# Brain_0_1_rv1.net
KiCad netlist of a schematic drawn in EAGLE
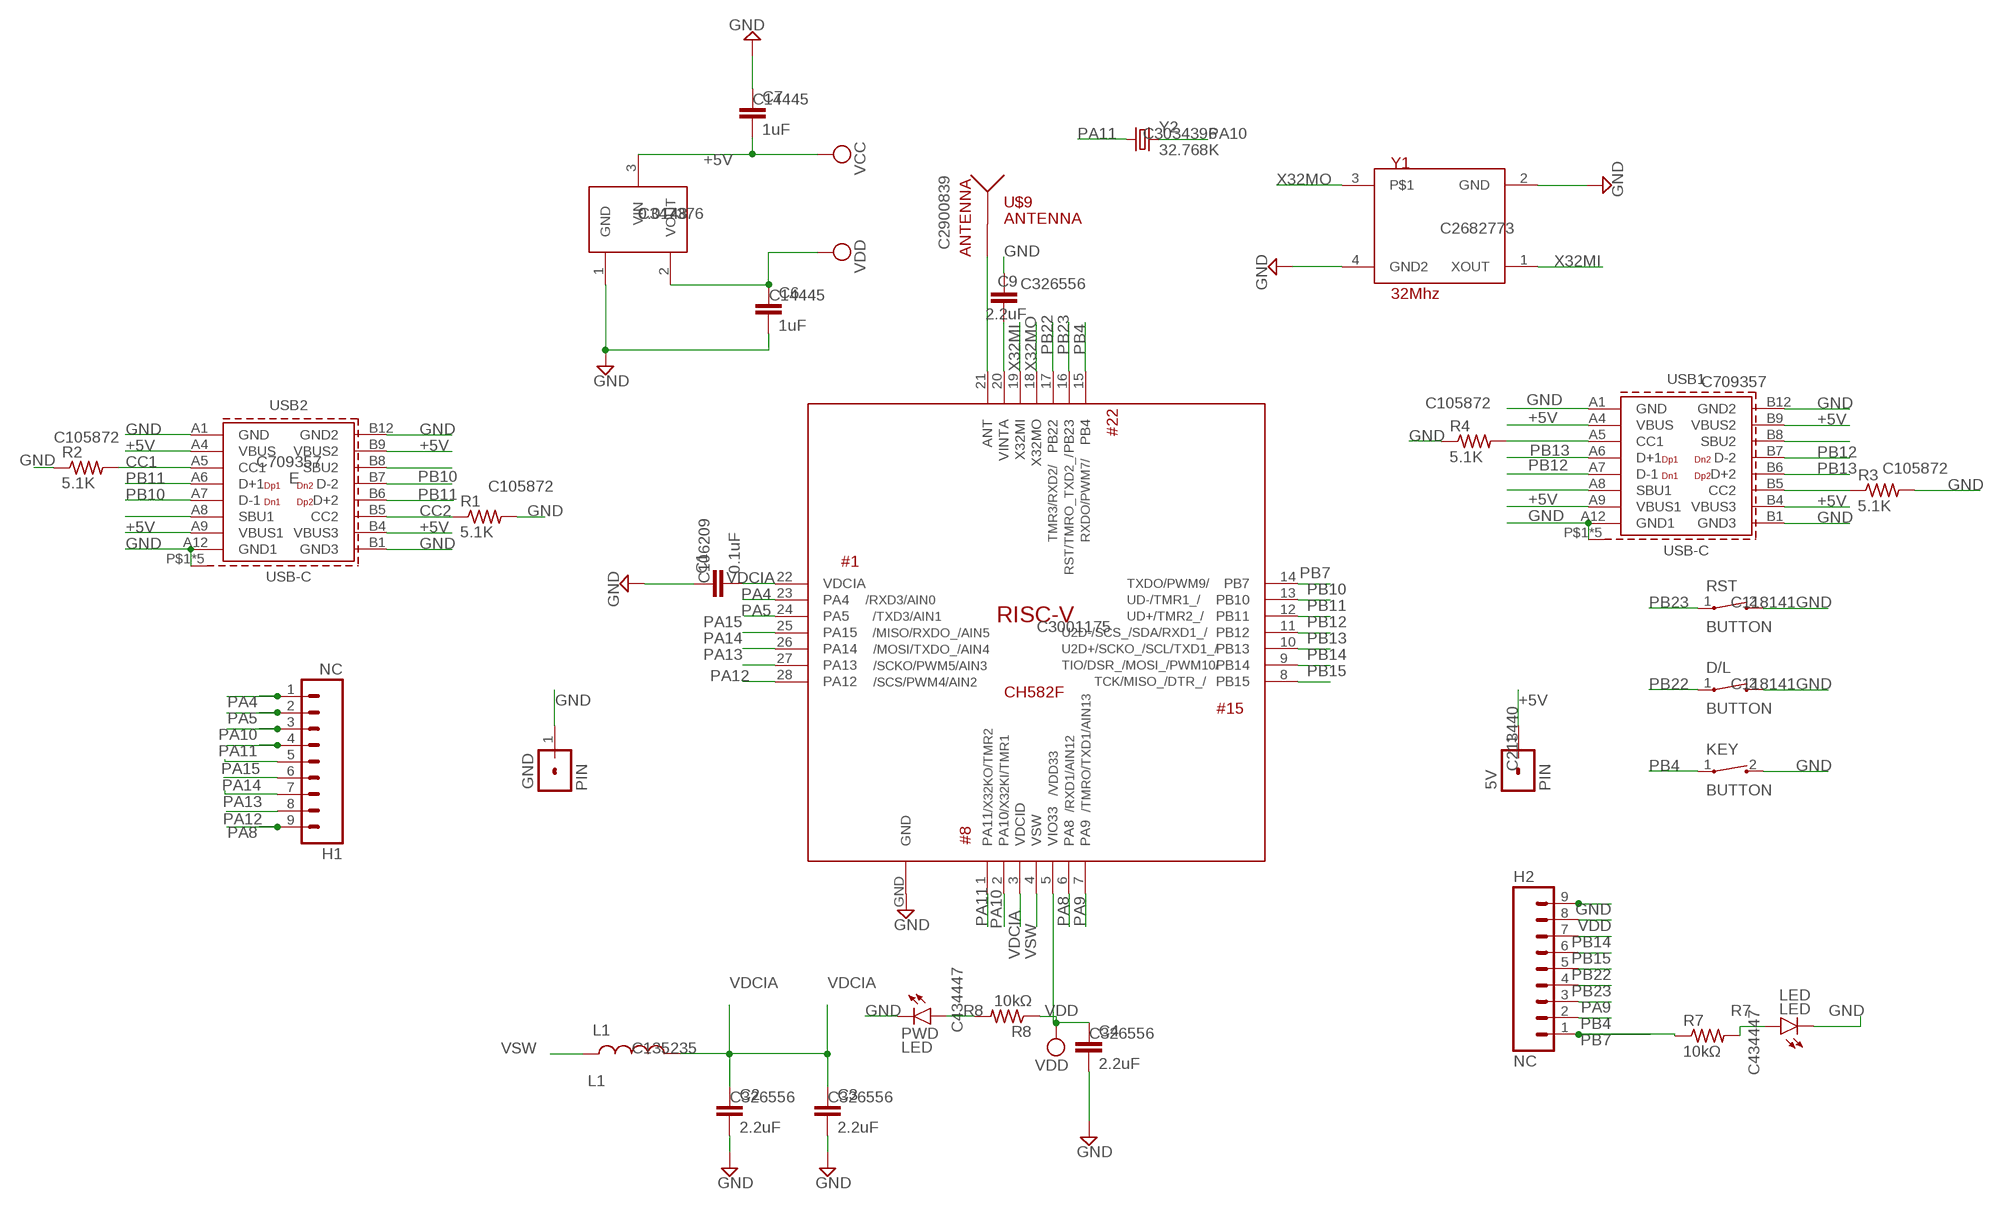
[diagram p0: schematic, sheet 1]

(export (version "E")
  (design (tool "Eeschema 10.0.6"))
  (components
    (comp (ref "5V")
      (value "PIN")
      (footprint "eagle-import:1X01")
      (fields (field (name "LCSC") "C213440"))
      (libsource (lib "eagle-import") (part "PIN"))
    )
    (comp (ref "C1")
      (value "0.1uF")
      (footprint "eagle-import:C1")
      (fields (field (name "LCSC") "C106209"))
      (libsource (lib "eagle-import") (part "C"))
    )
    (comp (ref "C2")
      (value "2.2uF")
      (footprint "eagle-import:C1")
      (fields (field (name "LCSC") "C326556"))
      (libsource (lib "eagle-import") (part "C"))
    )
    (comp (ref "C3")
      (value "2.2uF")
      (footprint "eagle-import:C1")
      (fields (field (name "LCSC") "C326556"))
      (libsource (lib "eagle-import") (part "C"))
    )
    (comp (ref "C4")
      (value "2.2uF")
      (footprint "eagle-import:C1")
      (fields (field (name "LCSC") "C326556"))
      (libsource (lib "eagle-import") (part "C"))
    )
    (comp (ref "C6")
      (value "1uF")
      (footprint "eagle-import:C1")
      (fields (field (name "LCSC") "C14445"))
      (libsource (lib "eagle-import") (part "C"))
    )
    (comp (ref "C7")
      (value "1uF")
      (footprint "eagle-import:C1")
      (fields (field (name "LCSC") "C14445"))
      (libsource (lib "eagle-import") (part "C"))
    )
    (comp (ref "C9")
      (value "2.2uF")
      (footprint "eagle-import:C1")
      (fields (field (name "LCSC") "C326556"))
      (libsource (lib "eagle-import") (part "C"))
    )
    (comp (ref "D/L")
      (value "BUTTON")
      (footprint "eagle-import:SOD8037X250N")
      (fields (field (name "LCSC") "C118141"))
      (libsource (lib "eagle-import") (part "BUTTON"))
    )
    (comp (ref "GND")
      (value "PIN")
      (footprint "eagle-import:1X01")
      (libsource (lib "eagle-import") (part "PIN"))
    )
    (comp (ref "H1")
      (value "NC")
      (footprint "eagle-import:61300911821")
      (libsource (lib "eagle-import") (part "H"))
    )
    (comp (ref "H2")
      (value "NC")
      (footprint "eagle-import:61300911821")
      (libsource (lib "eagle-import") (part "H"))
    )
    (comp (ref "KEY")
      (value "BUTTON")
      (footprint "eagle-import:SOD8037X250N")
      (libsource (lib "eagle-import") (part "BUTTON"))
    )
    (comp (ref "L1")
      (value "L1")
      (footprint "eagle-import:RESC3025X120N")
      (fields (field (name "LCSC") "C135235"))
      (libsource (lib "eagle-import") (part "L1"))
    )
    (comp (ref "LED")
      (value "LED")
      (footprint "eagle-import:CAPCP1005X40N")
      (fields (field (name "LCSC") "C434447"))
      (libsource (lib "eagle-import") (part "LED"))
    )
    (comp (ref "PWD")
      (value "LED")
      (footprint "eagle-import:CAPCP1005X40N")
      (fields (field (name "LCSC") "C434447"))
      (libsource (lib "eagle-import") (part "LED"))
    )
    (comp (ref "R1")
      (value "5.1K")
      (footprint "eagle-import:R0402")
      (fields (field (name "LCSC") "C105872"))
      (libsource (lib "eagle-import") (part "RR0402"))
    )
    (comp (ref "R2")
      (value "5.1K")
      (footprint "eagle-import:R0402")
      (fields (field (name "LCSC") "C105872"))
      (libsource (lib "eagle-import") (part "RR0402"))
    )
    (comp (ref "R3")
      (value "5.1K")
      (footprint "eagle-import:R0402")
      (fields (field (name "LCSC") "C105872"))
      (libsource (lib "eagle-import") (part "RR0402"))
    )
    (comp (ref "R4")
      (value "5.1K")
      (footprint "eagle-import:R0402")
      (fields (field (name "LCSC") "C105872"))
      (libsource (lib "eagle-import") (part "RR0402"))
    )
    (comp (ref "R7")
      (value "10kΩ")
      (footprint "eagle-import:R0402")
      (libsource (lib "eagle-import") (part "RR0402"))
    )
    (comp (ref "R8")
      (value "10kΩ")
      (footprint "eagle-import:R0402")
      (libsource (lib "eagle-import") (part "RR0402"))
    )
    (comp (ref "RST")
      (value "BUTTON")
      (footprint "eagle-import:SOD8037X250N")
      (fields (field (name "LCSC") "C118141"))
      (libsource (lib "eagle-import") (part "BUTTON"))
    )
    (comp (ref "U$8")
      (value "RISC-V")
      (footprint "eagle-import:QFN40P400X400X75-29T280N")
      (fields (field (name "LCSC") "C3001175"))
      (libsource (lib "eagle-import") (part "RISC-V"))
    )
    (comp (ref "U$9")
      (value "ANTENNA")
      (footprint "eagle-import:CAPCP3015X50N")
      (fields (field (name "LCSC") "C2900839"))
      (libsource (lib "eagle-import") (part "ANTENNA"))
    )
    (comp (ref "U1")
      (value "U1")
      (footprint "eagle-import:SOT95P240X90-3N")
      (fields (field (name "LCSC") "C347376") (field (name "PRICE-1000") "0.0148"))
      (libsource (lib "eagle-import") (part "U1"))
    )
    (comp (ref "USB1")
      (value "629722000214")
      (footprint "eagle-import:629722000214")
      (fields (field (name "LCSC") "C709357"))
      (libsource (lib "eagle-import") (part "J1"))
    )
    (comp (ref "USB2")
      (value "629722000214")
      (footprint "eagle-import:629722000214")
      (fields (field (name "LCSC") "C709357"))
      (libsource (lib "eagle-import") (part "J1"))
    )
    (comp (ref "Y1")
      (value "Y1YSX211SL")
      (footprint "eagle-import:OSCCC200X160X50N")
      (fields (field (name "LCSC") "C2682773"))
      (libsource (lib "eagle-import") (part "Y1YSX211SL"))
    )
    (comp (ref "Y2")
      (value "32.768K")
      (footprint "eagle-import:XTAL700X315X230N")
      (fields (field (name "LCSC") "C3034396"))
      (libsource (lib "eagle-import") (part "Y2"))
    )
  )
  (nets
    (net (code "1") (name "/CC1") (class "Default")
      (node (ref "R2") (pin "2") (pinfunction "2_2") (pintype "passive"))
      (node (ref "USB2") (pin "A5") (pinfunction "CC1_A5") (pintype "passive"))
    )
    (net (code "2") (name "/CC2") (class "Default")
      (node (ref "R1") (pin "1") (pinfunction "1_1") (pintype "passive"))
      (node (ref "USB2") (pin "B5") (pinfunction "CC2_B5") (pintype "passive"))
    )
    (net (code "3") (name "/PA4") (class "Default")
      (node (ref "H1") (pin "1") (pinfunction "1_1") (pintype "passive"))
      (node (ref "U$8") (pin "23") (pinfunction "PA4_23") (pintype "bidirectional"))
    )
    (net (code "4") (name "/PA5") (class "Default")
      (node (ref "H1") (pin "2") (pinfunction "2_2") (pintype "passive"))
      (node (ref "U$8") (pin "24") (pinfunction "PA5_24") (pintype "bidirectional"))
    )
    (net (code "5") (name "/PA8") (class "Default")
      (node (ref "H1") (pin "9") (pinfunction "9_9") (pintype "passive"))
      (node (ref "U$8") (pin "6") (pinfunction "PA8_6") (pintype "bidirectional"))
    )
    (net (code "6") (name "/PA9") (class "Default")
      (node (ref "H2") (pin "3") (pinfunction "3_3") (pintype "passive"))
      (node (ref "U$8") (pin "7") (pinfunction "PA9_7") (pintype "bidirectional"))
    )
    (net (code "7") (name "/PA10") (class "Default")
      (node (ref "H1") (pin "3") (pinfunction "3_3") (pintype "passive"))
      (node (ref "U$8") (pin "2") (pinfunction "PA10_2") (pintype "bidirectional"))
      (node (ref "Y2") (pin "2") (pinfunction "2_2") (pintype "passive"))
    )
    (net (code "8") (name "/PA11") (class "Default")
      (node (ref "H1") (pin "4") (pinfunction "4_4") (pintype "passive"))
      (node (ref "U$8") (pin "1") (pinfunction "PA11_1") (pintype "bidirectional"))
      (node (ref "Y2") (pin "1") (pinfunction "1_1") (pintype "passive"))
    )
    (net (code "9") (name "/PA12") (class "Default")
      (node (ref "H1") (pin "8") (pinfunction "8_8") (pintype "passive"))
      (node (ref "U$8") (pin "28") (pinfunction "PA12_28") (pintype "bidirectional"))
    )
    (net (code "10") (name "/PA13") (class "Default")
      (node (ref "H1") (pin "7") (pinfunction "7_7") (pintype "passive"))
      (node (ref "U$8") (pin "27") (pinfunction "PA13_27") (pintype "bidirectional"))
    )
    (net (code "11") (name "/PA14") (class "Default")
      (node (ref "H1") (pin "6") (pinfunction "6_6") (pintype "passive"))
      (node (ref "U$8") (pin "26") (pinfunction "PA14_26") (pintype "bidirectional"))
    )
    (net (code "12") (name "/PA15") (class "Default")
      (node (ref "H1") (pin "5") (pinfunction "5_5") (pintype "passive"))
      (node (ref "U$8") (pin "25") (pinfunction "PA15_25") (pintype "bidirectional"))
    )
    (net (code "13") (name "/PB4") (class "Default")
      (node (ref "H2") (pin "2") (pinfunction "2_2") (pintype "passive"))
      (node (ref "KEY") (pin "1") (pinfunction "1_1") (pintype "passive"))
      (node (ref "U$8") (pin "15") (pinfunction "PB4_15") (pintype "bidirectional"))
    )
    (net (code "14") (name "/PB7") (class "Default")
      (node (ref "H2") (pin "1") (pinfunction "1_1") (pintype "passive"))
      (node (ref "R7") (pin "1") (pinfunction "1_1") (pintype "passive"))
      (node (ref "U$8") (pin "14") (pinfunction "PB7_14") (pintype "bidirectional"))
    )
    (net (code "15") (name "/PB10") (class "Default")
      (node (ref "U$8") (pin "13") (pinfunction "PB10_13") (pintype "bidirectional"))
      (node (ref "USB2") (pin "A7") (pinfunction "D-1_A7") (pintype "passive"))
      (node (ref "USB2") (pin "B7") (pinfunction "D-2_B7") (pintype "passive"))
    )
    (net (code "16") (name "/PB11") (class "Default")
      (node (ref "U$8") (pin "12") (pinfunction "PB11_12") (pintype "bidirectional"))
      (node (ref "USB2") (pin "A6") (pinfunction "D+1_A6") (pintype "passive"))
      (node (ref "USB2") (pin "B6") (pinfunction "D+2_B6") (pintype "passive"))
    )
    (net (code "17") (name "/PB12") (class "Default")
      (node (ref "U$8") (pin "11") (pinfunction "PB12_11") (pintype "bidirectional"))
      (node (ref "USB1") (pin "A7") (pinfunction "D-1_A7") (pintype "passive"))
      (node (ref "USB1") (pin "B7") (pinfunction "D-2_B7") (pintype "passive"))
    )
    (net (code "18") (name "/PB13") (class "Default")
      (node (ref "U$8") (pin "10") (pinfunction "PB13_10") (pintype "bidirectional"))
      (node (ref "USB1") (pin "A6") (pinfunction "D+1_A6") (pintype "passive"))
      (node (ref "USB1") (pin "B6") (pinfunction "D+2_B6") (pintype "passive"))
    )
    (net (code "19") (name "/PB14") (class "Default")
      (node (ref "H2") (pin "7") (pinfunction "7_7") (pintype "passive"))
      (node (ref "U$8") (pin "9") (pinfunction "PB14_9") (pintype "bidirectional"))
    )
    (net (code "20") (name "/PB15") (class "Default")
      (node (ref "H2") (pin "6") (pinfunction "6_6") (pintype "passive"))
      (node (ref "U$8") (pin "8") (pinfunction "PB15_8") (pintype "bidirectional"))
    )
    (net (code "21") (name "/PB22") (class "Default")
      (node (ref "D/L") (pin "1") (pinfunction "1_1") (pintype "passive"))
      (node (ref "H2") (pin "5") (pinfunction "5_5") (pintype "passive"))
      (node (ref "U$8") (pin "17") (pinfunction "PB22_17") (pintype "bidirectional"))
    )
    (net (code "22") (name "/PB23") (class "Default")
      (node (ref "H2") (pin "4") (pinfunction "4_4") (pintype "passive"))
      (node (ref "RST") (pin "1") (pinfunction "1_1") (pintype "passive"))
      (node (ref "U$8") (pin "16") (pinfunction "PB23_16") (pintype "bidirectional"))
    )
    (net (code "23") (name "/R7") (class "Default")
      (node (ref "LED") (pin "A") (pinfunction "A_A") (pintype "passive"))
      (node (ref "R7") (pin "2") (pinfunction "2_2") (pintype "passive"))
    )
    (net (code "24") (name "/R8") (class "Default")
      (node (ref "PWD") (pin "A") (pinfunction "A_A") (pintype "passive"))
      (node (ref "R8") (pin "2") (pinfunction "2_2") (pintype "passive"))
    )
    (net (code "25") (name "/VDCIA") (class "Default")
      (node (ref "C1") (pin "2") (pinfunction "2_2") (pintype "passive"))
      (node (ref "C2") (pin "1") (pinfunction "1_1") (pintype "passive"))
      (node (ref "C3") (pin "1") (pinfunction "1_1") (pintype "passive"))
      (node (ref "L1") (pin "2") (pinfunction "2_2") (pintype "passive"))
      (node (ref "U$8") (pin "22") (pinfunction "VDCIA_22") (pintype "bidirectional"))
      (node (ref "U$8") (pin "3") (pinfunction "VDCID_3") (pintype "bidirectional"))
    )
    (net (code "26") (name "/VSW") (class "Default")
      (node (ref "L1") (pin "1") (pinfunction "1_1") (pintype "passive"))
      (node (ref "U$8") (pin "4") (pinfunction "VSW_4") (pintype "bidirectional"))
    )
    (net (code "27") (name "/X32MI") (class "Default")
      (node (ref "U$8") (pin "19") (pinfunction "X32MI_19") (pintype "bidirectional"))
      (node (ref "Y1") (pin "1") (pinfunction "XOUT_1") (pintype "bidirectional"))
    )
    (net (code "28") (name "/X32MO") (class "Default")
      (node (ref "U$8") (pin "18") (pinfunction "X32MO_18") (pintype "bidirectional"))
      (node (ref "Y1") (pin "3") (pinfunction "P$1_3") (pintype "bidirectional"))
    )
    (net (code "29") (name "GND") (class "Default")
      (node (ref "C1") (pin "1") (pinfunction "1_1") (pintype "passive"))
      (node (ref "C2") (pin "2") (pinfunction "2_2") (pintype "passive"))
      (node (ref "C3") (pin "2") (pinfunction "2_2") (pintype "passive"))
      (node (ref "C4") (pin "2") (pinfunction "2_2") (pintype "passive"))
      (node (ref "C6") (pin "2") (pinfunction "2_2") (pintype "passive"))
      (node (ref "C7") (pin "1") (pinfunction "1_1") (pintype "passive"))
      (node (ref "C9") (pin "1") (pinfunction "1_1") (pintype "passive"))
      (node (ref "D/L") (pin "2") (pinfunction "2_2") (pintype "passive"))
      (node (ref "GND") (pin "1") (pinfunction "1_1") (pintype "passive"))
      (node (ref "H2") (pin "9") (pinfunction "9_9") (pintype "passive"))
      (node (ref "KEY") (pin "2") (pinfunction "2_2") (pintype "passive"))
      (node (ref "LED") (pin "C") (pinfunction "C_C") (pintype "passive"))
      (node (ref "PWD") (pin "C") (pinfunction "C_C") (pintype "passive"))
      (node (ref "R1") (pin "2") (pinfunction "2_2") (pintype "passive"))
      (node (ref "R2") (pin "1") (pinfunction "1_1") (pintype "passive"))
      (node (ref "R3") (pin "2") (pinfunction "2_2") (pintype "passive"))
      (node (ref "R4") (pin "1") (pinfunction "1_1") (pintype "passive"))
      (node (ref "RST") (pin "2") (pinfunction "2_2") (pintype "passive"))
      (node (ref "U$8") (pin "GND") (pinfunction "GND_GND") (pintype "bidirectional"))
      (node (ref "U1") (pin "1") (pinfunction "GND_1") (pintype "bidirectional"))
      (node (ref "USB1") (pin "A1") (pinfunction "GND_A1") (pintype "passive"))
      (node (ref "USB1") (pin "A12") (pinfunction "GND1_A12") (pintype "passive"))
      (node (ref "USB1") (pin "B1") (pinfunction "GND3_B1") (pintype "passive"))
      (node (ref "USB1") (pin "B12") (pinfunction "GND2_B12") (pintype "passive"))
      (node (ref "USB1") (pin "P$1") (pinfunction "SHIELD_P$1") (pintype "passive"))
      (node (ref "USB1") (pin "S1") (pinfunction "SHIELD_S1") (pintype "passive"))
      (node (ref "USB1") (pin "S2") (pinfunction "SHIELD_S2") (pintype "passive"))
      (node (ref "USB1") (pin "S3") (pinfunction "SHIELD_S3") (pintype "passive"))
      (node (ref "USB1") (pin "S4") (pinfunction "SHIELD_S4") (pintype "passive"))
      (node (ref "USB2") (pin "A1") (pinfunction "GND_A1") (pintype "passive"))
      (node (ref "USB2") (pin "A12") (pinfunction "GND1_A12") (pintype "passive"))
      (node (ref "USB2") (pin "B1") (pinfunction "GND3_B1") (pintype "passive"))
      (node (ref "USB2") (pin "B12") (pinfunction "GND2_B12") (pintype "passive"))
      (node (ref "USB2") (pin "P$1") (pinfunction "SHIELD_P$1") (pintype "passive"))
      (node (ref "USB2") (pin "S1") (pinfunction "SHIELD_S1") (pintype "passive"))
      (node (ref "USB2") (pin "S2") (pinfunction "SHIELD_S2") (pintype "passive"))
      (node (ref "USB2") (pin "S3") (pinfunction "SHIELD_S3") (pintype "passive"))
      (node (ref "USB2") (pin "S4") (pinfunction "SHIELD_S4") (pintype "passive"))
      (node (ref "Y1") (pin "2") (pinfunction "GND_2") (pintype "bidirectional"))
      (node (ref "Y1") (pin "4") (pinfunction "GND2_4") (pintype "bidirectional"))
    )
    (net (code "30") (name "Net-(U$8-ANT)") (class "Default")
      (node (ref "U$8") (pin "21") (pinfunction "ANT_21") (pintype "bidirectional"))
      (node (ref "U$9") (pin "1") (pinfunction "P$1_1") (pintype "bidirectional"))
    )
    (net (code "31") (name "Net-(U$8-VINTA)") (class "Default")
      (node (ref "C9") (pin "2") (pinfunction "2_2") (pintype "passive"))
      (node (ref "U$8") (pin "20") (pinfunction "VINTA_20") (pintype "bidirectional"))
    )
    (net (code "32") (name "Net-(USB1-CC1)") (class "Default")
      (node (ref "R4") (pin "2") (pinfunction "2_2") (pintype "passive"))
      (node (ref "USB1") (pin "A5") (pinfunction "CC1_A5") (pintype "passive"))
    )
    (net (code "33") (name "Net-(USB1-CC2)") (class "Default")
      (node (ref "R3") (pin "1") (pinfunction "1_1") (pintype "passive"))
      (node (ref "USB1") (pin "B5") (pinfunction "CC2_B5") (pintype "passive"))
    )
    (net (code "34") (name "VCC") (class "Default")
      (node (ref "5V") (pin "1") (pinfunction "1_1") (pintype "passive"))
      (node (ref "C7") (pin "2") (pinfunction "2_2") (pintype "passive"))
      (node (ref "U1") (pin "3") (pinfunction "VIN_3") (pintype "input"))
      (node (ref "USB1") (pin "A4") (pinfunction "VBUS_A4") (pintype "passive"))
      (node (ref "USB1") (pin "A9") (pinfunction "VBUS1_A9") (pintype "passive"))
      (node (ref "USB1") (pin "B4") (pinfunction "VBUS3_B4") (pintype "passive"))
      (node (ref "USB1") (pin "B9") (pinfunction "VBUS2_B9") (pintype "passive"))
      (node (ref "USB2") (pin "A4") (pinfunction "VBUS_A4") (pintype "passive"))
      (node (ref "USB2") (pin "A9") (pinfunction "VBUS1_A9") (pintype "passive"))
      (node (ref "USB2") (pin "B4") (pinfunction "VBUS3_B4") (pintype "passive"))
      (node (ref "USB2") (pin "B9") (pinfunction "VBUS2_B9") (pintype "passive"))
    )
    (net (code "35") (name "VDD") (class "Default")
      (node (ref "C4") (pin "1") (pinfunction "1_1") (pintype "passive"))
      (node (ref "C6") (pin "1") (pinfunction "1_1") (pintype "passive"))
      (node (ref "H2") (pin "8") (pinfunction "8_8") (pintype "passive"))
      (node (ref "R8") (pin "1") (pinfunction "1_1") (pintype "passive"))
      (node (ref "U$8") (pin "5") (pinfunction "VIO33_5") (pintype "bidirectional"))
      (node (ref "U1") (pin "2") (pinfunction "VOUT_2") (pintype "output"))
    )
    (net (code "36") (name "unconnected-(U$9-P$2-Pad2)") (class "Default")
      (node (ref "U$9") (pin "2") (pinfunction "P$2_2") (pintype "bidirectional"))
    )
    (net (code "37") (name "unconnected-(USB1-SBU1-PadA8)") (class "Default")
      (node (ref "USB1") (pin "A8") (pinfunction "SBU1_A8") (pintype "passive"))
    )
    (net (code "38") (name "unconnected-(USB1-SBU2-PadB8)") (class "Default")
      (node (ref "USB1") (pin "B8") (pinfunction "SBU2_B8") (pintype "passive"))
    )
    (net (code "39") (name "unconnected-(USB2-SBU1-PadA8)") (class "Default")
      (node (ref "USB2") (pin "A8") (pinfunction "SBU1_A8") (pintype "passive"))
    )
    (net (code "40") (name "unconnected-(USB2-SBU2-PadB8)") (class "Default")
      (node (ref "USB2") (pin "B8") (pinfunction "SBU2_B8") (pintype "passive"))
    )
  )
)
